# sensor-3.net
KiCad netlist of a schematic drawn in Altium Designer
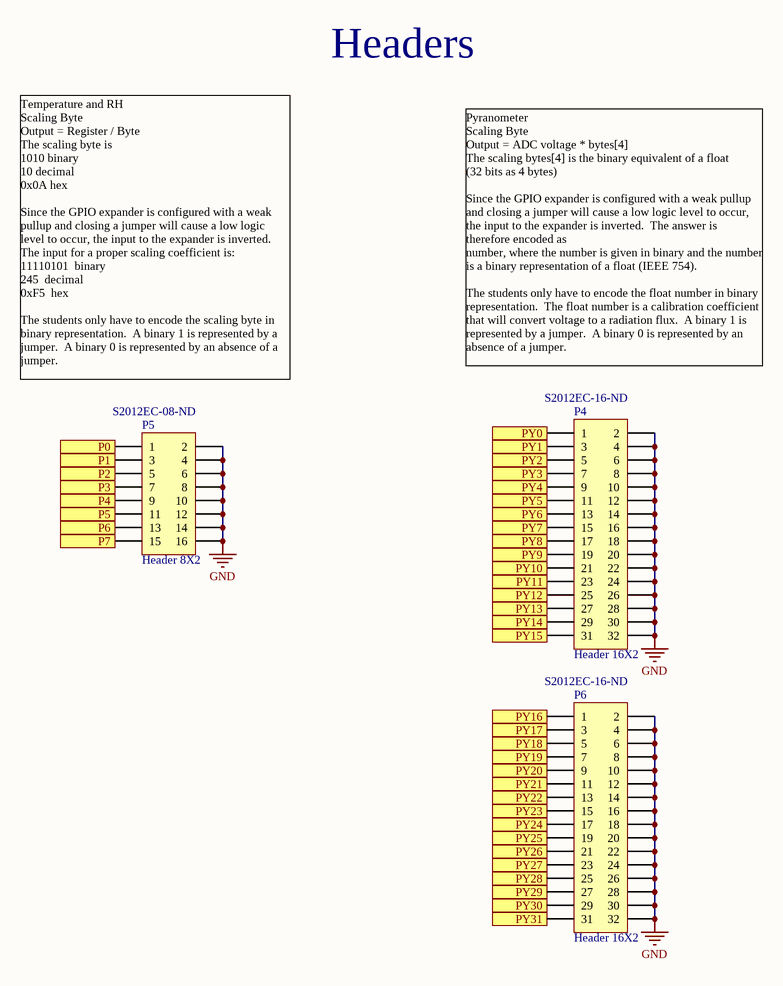
[diagram p0: sensor-3.SchDoc]

(export (version "E")
  (design (tool "Eeschema 10.0.6"))
  (components
    (comp (ref "P4")
      (value "Header 16X2")
      (footprint "HDR2X16")
      (description "Header, 16-Pin, Dual row")
      (fields
        (field (name "SUPPLIER PART NUMBER 1") "S2012EC-16-ND")
        (field (name "MANUFACTURER") "Sullins")
        (field (name "MANUFACTURER PART NUMBER") "PREC016DAAN-RC")
        (field (name "PUBLISHER") "Altium Limited")
      )
      (libsource (lib "Miscellaneous Connectors") (part "Header 16X2"))
    )
    (comp (ref "P5")
      (value "Header 8X2")
      (footprint "HDR2X8")
      (description "Header, 8-Pin, Dual row")
      (fields
        (field (name "SUPPLIER PART NUMBER 1") "S2012EC-08-ND")
        (field (name "MANUFACTURER") "Sullins")
        (field (name "MANUFACTURER PART NUMBER") "PREC008DAAN-RC")
        (field (name "PUBLISHER") "Altium Limited")
      )
      (libsource (lib "Miscellaneous Connectors") (part "Header 8X2"))
    )
    (comp (ref "P6")
      (value "Header 16X2")
      (footprint "HDR2X16")
      (description "Header, 16-Pin, Dual row")
      (fields
        (field (name "SUPPLIER PART NUMBER 1") "S2012EC-16-ND")
        (field (name "MANUFACTURER") "Sullins")
        (field (name "MANUFACTURER PART NUMBER") "PREC016DAAN-RC")
        (field (name "PUBLISHER") "Altium Limited")
      )
      (libsource (lib "Miscellaneous Connectors") (part "Header 16X2"))
    )
  )
  (nets
    (net (code "1") (name "/P0") (class "Default")
      (node (ref "P5") (pin "1") (pinfunction "1_1") (pintype "passive"))
    )
    (net (code "2") (name "/P1") (class "Default")
      (node (ref "P5") (pin "3") (pinfunction "3_3") (pintype "passive"))
    )
    (net (code "3") (name "/P2") (class "Default")
      (node (ref "P5") (pin "5") (pinfunction "5_5") (pintype "passive"))
    )
    (net (code "4") (name "/P3") (class "Default")
      (node (ref "P5") (pin "7") (pinfunction "7_7") (pintype "passive"))
    )
    (net (code "5") (name "/P4") (class "Default")
      (node (ref "P5") (pin "9") (pinfunction "9_9") (pintype "passive"))
    )
    (net (code "6") (name "/P5") (class "Default")
      (node (ref "P5") (pin "11") (pinfunction "11_11") (pintype "passive"))
    )
    (net (code "7") (name "/P6") (class "Default")
      (node (ref "P5") (pin "13") (pinfunction "13_13") (pintype "passive"))
    )
    (net (code "8") (name "/P7") (class "Default")
      (node (ref "P5") (pin "15") (pinfunction "15_15") (pintype "passive"))
    )
    (net (code "9") (name "/PY0") (class "Default")
      (node (ref "P4") (pin "1") (pinfunction "1_1") (pintype "passive"))
    )
    (net (code "10") (name "/PY1") (class "Default")
      (node (ref "P4") (pin "3") (pinfunction "3_3") (pintype "passive"))
    )
    (net (code "11") (name "/PY2") (class "Default")
      (node (ref "P4") (pin "5") (pinfunction "5_5") (pintype "passive"))
    )
    (net (code "12") (name "/PY3") (class "Default")
      (node (ref "P4") (pin "7") (pinfunction "7_7") (pintype "passive"))
    )
    (net (code "13") (name "/PY4") (class "Default")
      (node (ref "P4") (pin "9") (pinfunction "9_9") (pintype "passive"))
    )
    (net (code "14") (name "/PY5") (class "Default")
      (node (ref "P4") (pin "11") (pinfunction "11_11") (pintype "passive"))
    )
    (net (code "15") (name "/PY6") (class "Default")
      (node (ref "P4") (pin "13") (pinfunction "13_13") (pintype "passive"))
    )
    (net (code "16") (name "/PY7") (class "Default")
      (node (ref "P4") (pin "15") (pinfunction "15_15") (pintype "passive"))
    )
    (net (code "17") (name "/PY8") (class "Default")
      (node (ref "P4") (pin "17") (pinfunction "17_17") (pintype "passive"))
    )
    (net (code "18") (name "/PY9") (class "Default")
      (node (ref "P4") (pin "19") (pinfunction "19_19") (pintype "passive"))
    )
    (net (code "19") (name "/PY10") (class "Default")
      (node (ref "P4") (pin "21") (pinfunction "21_21") (pintype "passive"))
    )
    (net (code "20") (name "/PY11") (class "Default")
      (node (ref "P4") (pin "23") (pinfunction "23_23") (pintype "passive"))
    )
    (net (code "21") (name "/PY12") (class "Default")
      (node (ref "P4") (pin "25") (pinfunction "25_25") (pintype "passive"))
    )
    (net (code "22") (name "/PY13") (class "Default")
      (node (ref "P4") (pin "27") (pinfunction "27_27") (pintype "passive"))
    )
    (net (code "23") (name "/PY14") (class "Default")
      (node (ref "P4") (pin "29") (pinfunction "29_29") (pintype "passive"))
    )
    (net (code "24") (name "/PY15") (class "Default")
      (node (ref "P4") (pin "31") (pinfunction "31_31") (pintype "passive"))
    )
    (net (code "25") (name "/PY16") (class "Default")
      (node (ref "P6") (pin "1") (pinfunction "1_1") (pintype "passive"))
    )
    (net (code "26") (name "/PY17") (class "Default")
      (node (ref "P6") (pin "3") (pinfunction "3_3") (pintype "passive"))
    )
    (net (code "27") (name "/PY18") (class "Default")
      (node (ref "P6") (pin "5") (pinfunction "5_5") (pintype "passive"))
    )
    (net (code "28") (name "/PY19") (class "Default")
      (node (ref "P6") (pin "7") (pinfunction "7_7") (pintype "passive"))
    )
    (net (code "29") (name "/PY20") (class "Default")
      (node (ref "P6") (pin "9") (pinfunction "9_9") (pintype "passive"))
    )
    (net (code "30") (name "/PY21") (class "Default")
      (node (ref "P6") (pin "11") (pinfunction "11_11") (pintype "passive"))
    )
    (net (code "31") (name "/PY22") (class "Default")
      (node (ref "P6") (pin "13") (pinfunction "13_13") (pintype "passive"))
    )
    (net (code "32") (name "/PY23") (class "Default")
      (node (ref "P6") (pin "15") (pinfunction "15_15") (pintype "passive"))
    )
    (net (code "33") (name "/PY24") (class "Default")
      (node (ref "P6") (pin "17") (pinfunction "17_17") (pintype "passive"))
    )
    (net (code "34") (name "/PY25") (class "Default")
      (node (ref "P6") (pin "19") (pinfunction "19_19") (pintype "passive"))
    )
    (net (code "35") (name "/PY26") (class "Default")
      (node (ref "P6") (pin "21") (pinfunction "21_21") (pintype "passive"))
    )
    (net (code "36") (name "/PY27") (class "Default")
      (node (ref "P6") (pin "23") (pinfunction "23_23") (pintype "passive"))
    )
    (net (code "37") (name "/PY28") (class "Default")
      (node (ref "P6") (pin "25") (pinfunction "25_25") (pintype "passive"))
    )
    (net (code "38") (name "/PY29") (class "Default")
      (node (ref "P6") (pin "27") (pinfunction "27_27") (pintype "passive"))
    )
    (net (code "39") (name "/PY30") (class "Default")
      (node (ref "P6") (pin "29") (pinfunction "29_29") (pintype "passive"))
    )
    (net (code "40") (name "/PY31") (class "Default")
      (node (ref "P6") (pin "31") (pinfunction "31_31") (pintype "passive"))
    )
    (net (code "41") (name "GND") (class "Default")
      (node (ref "P4") (pin "10") (pinfunction "10_10") (pintype "passive"))
      (node (ref "P4") (pin "12") (pinfunction "12_12") (pintype "passive"))
      (node (ref "P4") (pin "14") (pinfunction "14_14") (pintype "passive"))
      (node (ref "P4") (pin "16") (pinfunction "16_16") (pintype "passive"))
      (node (ref "P4") (pin "18") (pinfunction "18_18") (pintype "passive"))
      (node (ref "P4") (pin "2") (pinfunction "2_2") (pintype "passive"))
      (node (ref "P4") (pin "20") (pinfunction "20_20") (pintype "passive"))
      (node (ref "P4") (pin "22") (pinfunction "22_22") (pintype "passive"))
      (node (ref "P4") (pin "24") (pinfunction "24_24") (pintype "passive"))
      (node (ref "P4") (pin "26") (pinfunction "26_26") (pintype "passive"))
      (node (ref "P4") (pin "28") (pinfunction "28_28") (pintype "passive"))
      (node (ref "P4") (pin "30") (pinfunction "30_30") (pintype "passive"))
      (node (ref "P4") (pin "32") (pinfunction "32_32") (pintype "passive"))
      (node (ref "P4") (pin "4") (pinfunction "4_4") (pintype "passive"))
      (node (ref "P4") (pin "6") (pinfunction "6_6") (pintype "passive"))
      (node (ref "P4") (pin "8") (pinfunction "8_8") (pintype "passive"))
      (node (ref "P5") (pin "10") (pinfunction "10_10") (pintype "passive"))
      (node (ref "P5") (pin "12") (pinfunction "12_12") (pintype "passive"))
      (node (ref "P5") (pin "14") (pinfunction "14_14") (pintype "passive"))
      (node (ref "P5") (pin "16") (pinfunction "16_16") (pintype "passive"))
      (node (ref "P5") (pin "2") (pinfunction "2_2") (pintype "passive"))
      (node (ref "P5") (pin "4") (pinfunction "4_4") (pintype "passive"))
      (node (ref "P5") (pin "6") (pinfunction "6_6") (pintype "passive"))
      (node (ref "P5") (pin "8") (pinfunction "8_8") (pintype "passive"))
      (node (ref "P6") (pin "10") (pinfunction "10_10") (pintype "passive"))
      (node (ref "P6") (pin "12") (pinfunction "12_12") (pintype "passive"))
      (node (ref "P6") (pin "14") (pinfunction "14_14") (pintype "passive"))
      (node (ref "P6") (pin "16") (pinfunction "16_16") (pintype "passive"))
      (node (ref "P6") (pin "18") (pinfunction "18_18") (pintype "passive"))
      (node (ref "P6") (pin "2") (pinfunction "2_2") (pintype "passive"))
      (node (ref "P6") (pin "20") (pinfunction "20_20") (pintype "passive"))
      (node (ref "P6") (pin "22") (pinfunction "22_22") (pintype "passive"))
      (node (ref "P6") (pin "24") (pinfunction "24_24") (pintype "passive"))
      (node (ref "P6") (pin "26") (pinfunction "26_26") (pintype "passive"))
      (node (ref "P6") (pin "28") (pinfunction "28_28") (pintype "passive"))
      (node (ref "P6") (pin "30") (pinfunction "30_30") (pintype "passive"))
      (node (ref "P6") (pin "32") (pinfunction "32_32") (pintype "passive"))
      (node (ref "P6") (pin "4") (pinfunction "4_4") (pintype "passive"))
      (node (ref "P6") (pin "6") (pinfunction "6_6") (pintype "passive"))
      (node (ref "P6") (pin "8") (pinfunction "8_8") (pintype "passive"))
    )
  )
)
